# SX1250.net
KiCad netlist of a schematic drawn in Altium Designer
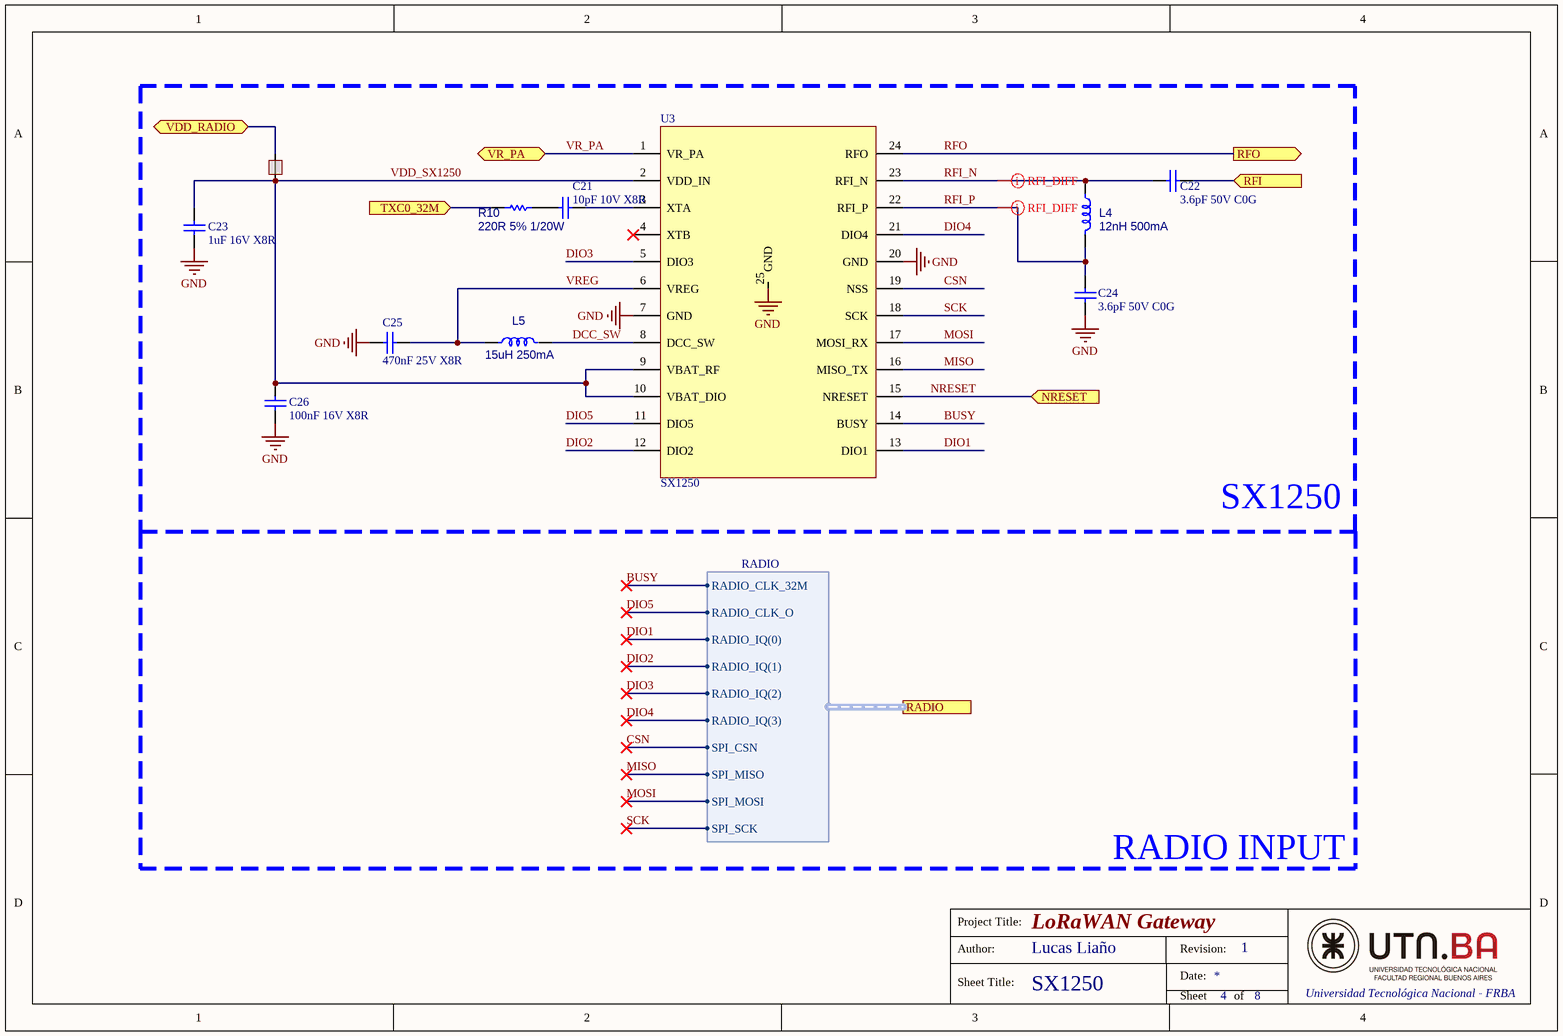
[diagram p0: SX1250.SchDoc]

(export (version "E")
  (design (tool "Eeschema 10.0.6"))
  (components
    (comp (ref "C21")
      (value "10pF 10V X8R")
      (footprint "C_0603")
      (description "Capacitor")
      (fields (field (name "MPN") "C0603X100J8HACAUTO") (field (name "MANUFACTURER") "KEMET"))
      (libsource (lib "lorawan_gateway") (part "Cap"))
    )
    (comp (ref "C22")
      (value "3.6pF 50V C0G")
      (footprint "C_0603")
      (description "Capacitor")
      (fields (field (name "MPN") "GJM0335C1H3R6WB01") (field (name "MANUFACTURER") "Murata Electronics"))
      (libsource (lib "lorawan_gateway") (part "Cap"))
    )
    (comp (ref "C23")
      (value "1uF 16V X8R")
      (footprint "C_0603")
      (description "Capacitor")
      (fields (field (name "MPN") "CGA4J3X8R1C105K125AB") (field (name "MANUFACTURER") "TDK Corporation"))
      (libsource (lib "lorawan_gateway") (part "Cap"))
    )
    (comp (ref "C24")
      (value "3.6pF 50V C0G")
      (footprint "C_0603")
      (description "Capacitor")
      (fields (field (name "MPN") "GJM0335C1H3R6WB01") (field (name "MANUFACTURER") "Murata Electronics"))
      (libsource (lib "lorawan_gateway") (part "Cap"))
    )
    (comp (ref "C25")
      (value "470nF 25V X8R")
      (footprint "C_0603")
      (description "Capacitor")
      (fields (field (name "MPN") "VJ0603H472JXXAC") (field (name "MANUFACTURER") "Vishay"))
      (libsource (lib "lorawan_gateway") (part "Cap"))
    )
    (comp (ref "C26")
      (value "100nF 16V X8R")
      (footprint "C_0603")
      (description "Capacitor")
      (fields (field (name "MPN") "C1206C104K4HACAUTO") (field (name "MANUFACTURER") "KEMET"))
      (libsource (lib "lorawan_gateway") (part "Cap"))
    )
    (comp (ref "L4")
      (value "12nH 500mA")
      (footprint "L_0402")
      (description "Inductor")
      (fields (field (name "MANUFACTURER") "Murata Electronics") (field (name "MPN") "LQW15AN12NH00D"))
      (libsource (lib "lorawan_gateway") (part "IND"))
    )
    (comp (ref "L5")
      (value "15uH 250mA")
      (footprint "0805[2012]")
      (description "FIXED IND 15UH 250MA 950MOHM SMD")
      (fields (field (name "MANUFACTURER") "TDK Corporation") (field (name "MPN") "MLZ2012M150WT000"))
      (libsource (lib "lorawan_gateway") (part "IND"))
    )
    (comp (ref "NT16")
      (value "NT")
      (footprint "NTIE24")
      (description "NET_TIE")
      (libsource (lib "lorawan_gateway") (part "NTIE"))
    )
    (comp (ref "R10")
      (value "220R 5% 1/20W")
      (footprint "0603[1608]")
      (description "Resistor")
      (fields
        (field (name "MANUFACTURER") "Panasonic Electronic Components")
        (field (name "MPN") "ERJ-1GNJ221C")
      )
      (libsource (lib "lorawan_gateway") (part "Res"))
    )
    (comp (ref "U3")
      (value "SX1250")
      (footprint "vqfn24_4x4mm")
      (description "SX1250 - Ultra low power RF Front-End")
      (fields (field (name "MANUFACTURER") "Semtech") (field (name "MPN") "SX1250IMLTRT"))
      (libsource (lib "lorawan_gateway") (part "SX1250"))
    )
  )
  (nets
    (net (code "2") (name "/BUSY") (class "Default")
      (node (ref "U3") (pin "14") (pinfunction "BUSY_14") (pintype "passive"))
    )
    (net (code "3") (name "/CSN") (class "Default")
      (node (ref "U3") (pin "19") (pinfunction "NSS_19") (pintype "passive"))
    )
    (net (code "4") (name "/DCC_SW") (class "Default")
      (node (ref "L5") (pin "2") (pinfunction "2_2") (pintype "passive"))
      (node (ref "U3") (pin "8") (pinfunction "DCC_SW_8") (pintype "passive"))
    )
    (net (code "5") (name "/DIO1") (class "Default")
      (node (ref "U3") (pin "13") (pinfunction "DIO1_13") (pintype "passive+no_connect"))
    )
    (net (code "6") (name "/DIO2") (class "Default")
      (node (ref "U3") (pin "12") (pinfunction "DIO2_12") (pintype "passive+no_connect"))
    )
    (net (code "7") (name "/DIO3") (class "Default")
      (node (ref "U3") (pin "5") (pinfunction "DIO3_5") (pintype "passive+no_connect"))
    )
    (net (code "8") (name "/DIO4") (class "Default")
      (node (ref "U3") (pin "21") (pinfunction "DIO4_21") (pintype "passive+no_connect"))
    )
    (net (code "9") (name "/DIO5") (class "Default")
      (node (ref "U3") (pin "11") (pinfunction "DIO5_11") (pintype "passive+no_connect"))
    )
    (net (code "10") (name "/MISO") (class "Default")
      (node (ref "U3") (pin "16") (pinfunction "MISO_TX_16") (pintype "passive"))
    )
    (net (code "11") (name "/MOSI") (class "Default")
      (node (ref "U3") (pin "17") (pinfunction "MOSI_RX_17") (pintype "passive"))
    )
    (net (code "12") (name "/NRESET") (class "Default")
      (node (ref "U3") (pin "15") (pinfunction "NRESET_15") (pintype "passive"))
    )
    (net (code "13") (name "/RFI") (class "Default")
      (node (ref "C22") (pin "2") (pinfunction "2_2") (pintype "passive"))
    )
    (net (code "14") (name "/RFI_N") (class "Default")
      (node (ref "C22") (pin "1") (pinfunction "1_1") (pintype "passive"))
      (node (ref "L4") (pin "1") (pinfunction "1_1") (pintype "passive"))
      (node (ref "U3") (pin "23") (pinfunction "RFI_N_23") (pintype "passive"))
    )
    (net (code "15") (name "/RFI_P") (class "Default")
      (node (ref "C24") (pin "1") (pinfunction "1_1") (pintype "passive"))
      (node (ref "L4") (pin "2") (pinfunction "2_2") (pintype "passive"))
      (node (ref "U3") (pin "22") (pinfunction "RFI_P_22") (pintype "passive"))
    )
    (net (code "16") (name "/RFO") (class "Default")
      (node (ref "U3") (pin "24") (pinfunction "RFO_24") (pintype "passive"))
    )
    (net (code "17") (name "/SCK") (class "Default")
      (node (ref "U3") (pin "18") (pinfunction "SCK_18") (pintype "passive"))
    )
    (net (code "18") (name "/TXC0_32M") (class "Default")
      (node (ref "R10") (pin "1") (pinfunction "1_1") (pintype "passive"))
    )
    (net (code "19") (name "/VDD_RADIO") (class "Default")
      (node (ref "NT16") (pin "2") (pinfunction "2_2") (pintype "passive"))
    )
    (net (code "20") (name "/VDD_SX1250") (class "Default")
      (node (ref "C23") (pin "1") (pinfunction "1_1") (pintype "passive"))
      (node (ref "C26") (pin "1") (pinfunction "1_1") (pintype "passive"))
      (node (ref "NT16") (pin "1") (pinfunction "1_1") (pintype "passive"))
      (node (ref "U3") (pin "10") (pinfunction "VBAT_DIO_10") (pintype "power_in"))
      (node (ref "U3") (pin "2") (pinfunction "VDD_IN_2") (pintype "passive"))
      (node (ref "U3") (pin "9") (pinfunction "VBAT_RF_9") (pintype "power_in"))
    )
    (net (code "21") (name "/VREG") (class "Default")
      (node (ref "C25") (pin "1") (pinfunction "1_1") (pintype "passive"))
      (node (ref "L5") (pin "1") (pinfunction "1_1") (pintype "passive"))
      (node (ref "U3") (pin "6") (pinfunction "VREG_6") (pintype "power_in"))
    )
    (net (code "22") (name "/VR_PA") (class "Default")
      (node (ref "U3") (pin "1") (pinfunction "VR_PA_1") (pintype "passive"))
    )
    (net (code "24") (name "GND") (class "Default")
      (node (ref "C23") (pin "2") (pinfunction "2_2") (pintype "passive"))
      (node (ref "C24") (pin "2") (pinfunction "2_2") (pintype "passive"))
      (node (ref "C25") (pin "2") (pinfunction "2_2") (pintype "passive"))
      (node (ref "C26") (pin "2") (pinfunction "2_2") (pintype "passive"))
      (node (ref "U3") (pin "20") (pinfunction "GND_20") (pintype "power_in"))
      (node (ref "U3") (pin "25") (pinfunction "GND_25") (pintype "power_in"))
      (node (ref "U3") (pin "7") (pinfunction "GND_7") (pintype "power_in"))
    )
    (net (code "25") (name "Net-(C21-Pad2)") (class "Default")
      (node (ref "C21") (pin "2") (pinfunction "2_2") (pintype "passive"))
      (node (ref "R10") (pin "2") (pinfunction "2_2") (pintype "passive"))
    )
    (net (code "26") (name "Net-(U3-XTA)") (class "Default")
      (node (ref "C21") (pin "1") (pinfunction "1_1") (pintype "passive"))
      (node (ref "U3") (pin "3") (pinfunction "XTA_3") (pintype "passive"))
    )
    (net (code "27") (name "unconnected-(U3-XTB-Pad4)") (class "Default")
      (node (ref "U3") (pin "4") (pinfunction "XTB_4") (pintype "passive+no_connect"))
    )
  )
)
